# fpga.net
KiCad netlist of a schematic drawn in Altium Designer
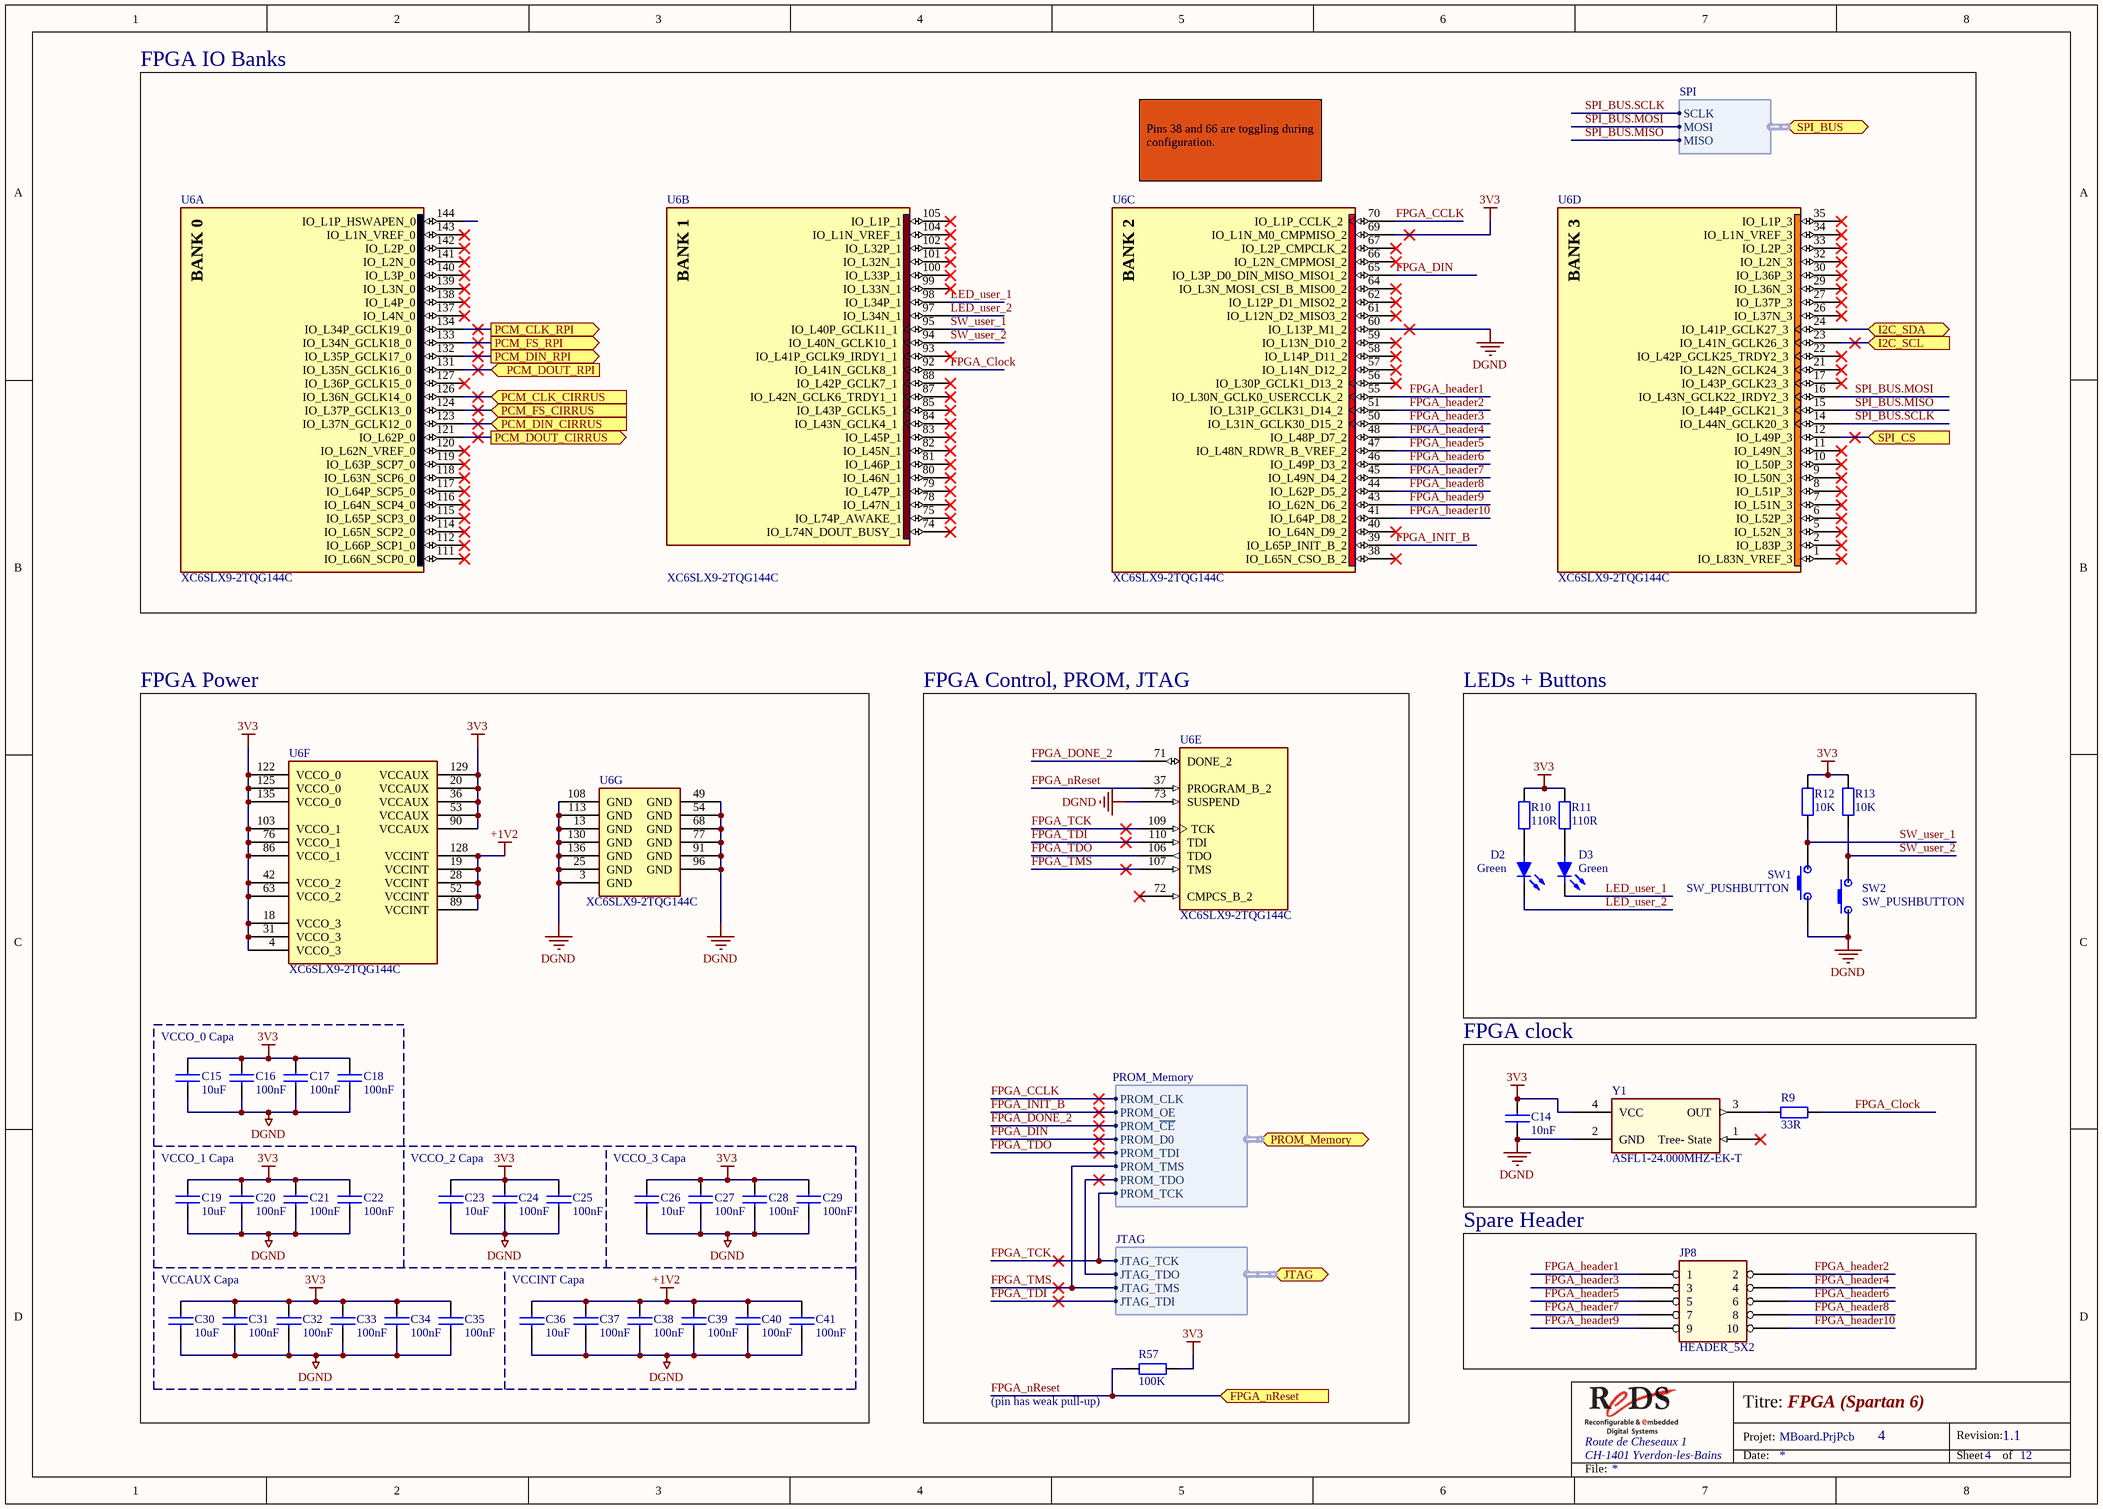
[diagram p0: fpga.SchDoc]

(export (version "E")
  (design (tool "Eeschema 10.0.6"))
  (components
    (comp (ref "C14")
      (value "10nF")
      (footprint "SM/C_0603")
      (description "Capacitor, ceramic")
      (fields (field (name "MANUFACTURER") "Kemet ") (field (name "VOLTAGE") "50V"))
      (libsource (lib "Database_heig-vd") (part "Cap"))
    )
    (comp (ref "C15")
      (value "10uF")
      (footprint "SM/C_1206")
      (description "Chip Monolithic Ceramic Capacitor")
      (fields (field (name "MANUFACTURER") "muRata") (field (name "VOLTAGE") "35V"))
      (libsource (lib "Database_heig-vd") (part "Cap"))
    )
    (comp (ref "C16")
      (value "100nF")
      (footprint "SM/C_0603")
      (description "Ceramic multi-layer")
      (fields (field (name "MANUFACTURER") "AVX") (field (name "VOLTAGE") "16V"))
      (libsource (lib "Database_heig-vd") (part "Cap"))
    )
    (comp (ref "C17")
      (value "100nF")
      (footprint "SM/C_0603")
      (description "Ceramic multi-layer")
      (fields (field (name "MANUFACTURER") "AVX") (field (name "VOLTAGE") "16V"))
      (libsource (lib "Database_heig-vd") (part "Cap"))
    )
    (comp (ref "C18")
      (value "100nF")
      (footprint "SM/C_0603")
      (description "Ceramic multi-layer")
      (fields (field (name "MANUFACTURER") "AVX") (field (name "VOLTAGE") "16V"))
      (libsource (lib "Database_heig-vd") (part "Cap"))
    )
    (comp (ref "C19")
      (value "10uF")
      (footprint "SM/C_1206")
      (description "Chip Monolithic Ceramic Capacitor")
      (fields (field (name "MANUFACTURER") "muRata") (field (name "VOLTAGE") "35V"))
      (libsource (lib "Database_heig-vd") (part "Cap"))
    )
    (comp (ref "C20")
      (value "100nF")
      (footprint "SM/C_0603")
      (description "Ceramic multi-layer")
      (fields (field (name "MANUFACTURER") "AVX") (field (name "VOLTAGE") "16V"))
      (libsource (lib "Database_heig-vd") (part "Cap"))
    )
    (comp (ref "C21")
      (value "100nF")
      (footprint "SM/C_0603")
      (description "Ceramic multi-layer")
      (fields (field (name "MANUFACTURER") "AVX") (field (name "VOLTAGE") "16V"))
      (libsource (lib "Database_heig-vd") (part "Cap"))
    )
    (comp (ref "C22")
      (value "100nF")
      (footprint "SM/C_0603")
      (description "Ceramic multi-layer")
      (fields (field (name "MANUFACTURER") "AVX") (field (name "VOLTAGE") "16V"))
      (libsource (lib "Database_heig-vd") (part "Cap"))
    )
    (comp (ref "C23")
      (value "10uF")
      (footprint "SM/C_1206")
      (description "Chip Monolithic Ceramic Capacitor")
      (fields (field (name "MANUFACTURER") "muRata") (field (name "VOLTAGE") "35V"))
      (libsource (lib "Database_heig-vd") (part "Cap"))
    )
    (comp (ref "C24")
      (value "100nF")
      (footprint "SM/C_0603")
      (description "Ceramic multi-layer")
      (fields (field (name "MANUFACTURER") "AVX") (field (name "VOLTAGE") "16V"))
      (libsource (lib "Database_heig-vd") (part "Cap"))
    )
    (comp (ref "C25")
      (value "100nF")
      (footprint "SM/C_0603")
      (description "Ceramic multi-layer")
      (fields (field (name "MANUFACTURER") "AVX") (field (name "VOLTAGE") "16V"))
      (libsource (lib "Database_heig-vd") (part "Cap"))
    )
    (comp (ref "C26")
      (value "10uF")
      (footprint "SM/C_1206")
      (description "Chip Monolithic Ceramic Capacitor")
      (fields (field (name "MANUFACTURER") "muRata") (field (name "VOLTAGE") "35V"))
      (libsource (lib "Database_heig-vd") (part "Cap"))
    )
    (comp (ref "C27")
      (value "100nF")
      (footprint "SM/C_0603")
      (description "Ceramic multi-layer")
      (fields (field (name "MANUFACTURER") "AVX") (field (name "VOLTAGE") "16V"))
      (libsource (lib "Database_heig-vd") (part "Cap"))
    )
    (comp (ref "C28")
      (value "100nF")
      (footprint "SM/C_0603")
      (description "Ceramic multi-layer")
      (fields (field (name "MANUFACTURER") "AVX") (field (name "VOLTAGE") "16V"))
      (libsource (lib "Database_heig-vd") (part "Cap"))
    )
    (comp (ref "C29")
      (value "100nF")
      (footprint "SM/C_0603")
      (description "Ceramic multi-layer")
      (fields (field (name "MANUFACTURER") "AVX") (field (name "VOLTAGE") "16V"))
      (libsource (lib "Database_heig-vd") (part "Cap"))
    )
    (comp (ref "C30")
      (value "10uF")
      (footprint "SM/C_1206")
      (description "Chip Monolithic Ceramic Capacitor")
      (fields (field (name "MANUFACTURER") "muRata") (field (name "VOLTAGE") "35V"))
      (libsource (lib "Database_heig-vd") (part "Cap"))
    )
    (comp (ref "C31")
      (value "100nF")
      (footprint "SM/C_0603")
      (description "Ceramic multi-layer")
      (fields (field (name "MANUFACTURER") "AVX") (field (name "VOLTAGE") "16V"))
      (libsource (lib "Database_heig-vd") (part "Cap"))
    )
    (comp (ref "C32")
      (value "100nF")
      (footprint "SM/C_0603")
      (description "Ceramic multi-layer")
      (fields (field (name "MANUFACTURER") "AVX") (field (name "VOLTAGE") "16V"))
      (libsource (lib "Database_heig-vd") (part "Cap"))
    )
    (comp (ref "C33")
      (value "100nF")
      (footprint "SM/C_0603")
      (description "Ceramic multi-layer")
      (fields (field (name "MANUFACTURER") "AVX") (field (name "VOLTAGE") "16V"))
      (libsource (lib "Database_heig-vd") (part "Cap"))
    )
    (comp (ref "C34")
      (value "100nF")
      (footprint "SM/C_0603")
      (description "Ceramic multi-layer")
      (fields (field (name "MANUFACTURER") "AVX") (field (name "VOLTAGE") "16V"))
      (libsource (lib "Database_heig-vd") (part "Cap"))
    )
    (comp (ref "C35")
      (value "100nF")
      (footprint "SM/C_0603")
      (description "Ceramic multi-layer")
      (fields (field (name "MANUFACTURER") "AVX") (field (name "VOLTAGE") "16V"))
      (libsource (lib "Database_heig-vd") (part "Cap"))
    )
    (comp (ref "C36")
      (value "10uF")
      (footprint "SM/C_1206")
      (description "Chip Monolithic Ceramic Capacitor")
      (fields (field (name "MANUFACTURER") "muRata") (field (name "VOLTAGE") "35V"))
      (libsource (lib "Database_heig-vd") (part "Cap"))
    )
    (comp (ref "C37")
      (value "100nF")
      (footprint "SM/C_0603")
      (description "Ceramic multi-layer")
      (fields (field (name "MANUFACTURER") "AVX") (field (name "VOLTAGE") "16V"))
      (libsource (lib "Database_heig-vd") (part "Cap"))
    )
    (comp (ref "C38")
      (value "100nF")
      (footprint "SM/C_0603")
      (description "Ceramic multi-layer")
      (fields (field (name "MANUFACTURER") "AVX") (field (name "VOLTAGE") "16V"))
      (libsource (lib "Database_heig-vd") (part "Cap"))
    )
    (comp (ref "C39")
      (value "100nF")
      (footprint "SM/C_0603")
      (description "Ceramic multi-layer")
      (fields (field (name "MANUFACTURER") "AVX") (field (name "VOLTAGE") "16V"))
      (libsource (lib "Database_heig-vd") (part "Cap"))
    )
    (comp (ref "C40")
      (value "100nF")
      (footprint "SM/C_0603")
      (description "Ceramic multi-layer")
      (fields (field (name "MANUFACTURER") "AVX") (field (name "VOLTAGE") "16V"))
      (libsource (lib "Database_heig-vd") (part "Cap"))
    )
    (comp (ref "C41")
      (value "100nF")
      (footprint "SM/C_0603")
      (description "Ceramic multi-layer")
      (fields (field (name "MANUFACTURER") "AVX") (field (name "VOLTAGE") "16V"))
      (libsource (lib "Database_heig-vd") (part "Cap"))
    )
    (comp (ref "D2")
      (value "Green")
      (footprint "PLCC_2")
      (description "SMT LED Green, Single Color PLCC-2 Type")
      (fields (field (name "MANUFACTURER") "Broadcom/Avago") (field (name "VOLTAGE") "2,2V"))
      (libsource (lib "Database_heig-vd") (part "Led"))
    )
    (comp (ref "D3")
      (value "Green")
      (footprint "PLCC_2")
      (description "SMT LED Green, Single Color PLCC-2 Type")
      (fields (field (name "MANUFACTURER") "Broadcom/Avago") (field (name "VOLTAGE") "2,2V"))
      (libsource (lib "Database_heig-vd") (part "Led"))
    )
    (comp (ref "JP8")
      (value "HEADER_5X2")
      (footprint "BLKCON.100/VH/TM2OE/W.200/10")
      (description "Barrette double 2x5 poles 2.54mm")
      (fields (field (name "MANUFACTURER") "TE Connectivity"))
      (libsource (lib "Database_heig-vd") (part "HEADER_5X2"))
    )
    (comp (ref "R9")
      (value "33R")
      (footprint "SM/R_0603")
      (description "Résistance 0603 63mW 1% 33R")
      (fields (field (name "MANUFACTURER") "Multicomp") (field (name "POWER") "63mW"))
      (libsource (lib "Database_heig-vd") (part "Res"))
    )
    (comp (ref "R10")
      (value "110R")
      (footprint "SM/R_0603")
      (description "Résistance 0603 63mW 1% 110R")
      (fields (field (name "MANUFACTURER") "Multicomp") (field (name "POWER") "63mW"))
      (libsource (lib "Database_heig-vd") (part "Res"))
    )
    (comp (ref "R11")
      (value "110R")
      (footprint "SM/R_0603")
      (description "Résistance 0603 63mW 1% 110R")
      (fields (field (name "MANUFACTURER") "Multicomp") (field (name "POWER") "63mW"))
      (libsource (lib "Database_heig-vd") (part "Res"))
    )
    (comp (ref "R12")
      (value "10K")
      (footprint "SM/R_0603")
      (description "Résistance 0603 63mW 1% 10K")
      (fields (field (name "MANUFACTURER") "Multicomp") (field (name "POWER") "63mW"))
      (libsource (lib "Database_heig-vd") (part "Res"))
    )
    (comp (ref "R13")
      (value "10K")
      (footprint "SM/R_0603")
      (description "Résistance 0603 63mW 1% 10K")
      (fields (field (name "MANUFACTURER") "Multicomp") (field (name "POWER") "63mW"))
      (libsource (lib "Database_heig-vd") (part "Res"))
    )
    (comp (ref "R57")
      (value "100K")
      (footprint "SM/R_0603")
      (description "Résistance 0603 63mW 1% 100K")
      (fields (field (name "MANUFACTURER") "Multicomp") (field (name "POWER") "63mW"))
      (libsource (lib "Database_heig-vd") (part "Res"))
    )
    (comp (ref "SW1")
      (value "SW_PUSHBUTTON")
      (footprint "TE Connectivity_SWITCH_SERIES-FSMSM")
      (description "SWITCH TACTILE SPST-NO 0.05A 12V")
      (fields (field (name "MANUFACTURER") "TE Connectivity") (field (name "VOLTAGE") "12V"))
      (libsource (lib "Database_heig-vd") (part "SW_PUSHBUTTON"))
    )
    (comp (ref "SW2")
      (value "SW_PUSHBUTTON")
      (footprint "TE Connectivity_SWITCH_SERIES-FSMSM")
      (description "SWITCH TACTILE SPST-NO 0.05A 12V")
      (fields (field (name "MANUFACTURER") "TE Connectivity") (field (name "VOLTAGE") "12V"))
      (libsource (lib "Database_heig-vd") (part "SW_PUSHBUTTON"))
    )
    (comp (ref "U6")
      (value "XC6SLX9-2TQG144C")
      (footprint "TQFP-144")
      (fields (field (name "MANUFACTURER") "Xilinx"))
      (libsource (lib "Database_heig-vd") (part "XC6SLX9-2TQG144C"))
    )
    (comp (ref "Y1")
      (value "OSCILLATOR_2")
      (footprint "ABRACON_OSCILLATOR_ASFL1 SERIES")
      (description "Oscillateur SMD 5mmx3.2mmx0.85mm")
      (fields
        (field (name "MANUFACTURER") "ABRACON Corporation")
        (field (name "MANUFACTURER P/N") "ASFL1-24.000MHZ-EK-T")
        (field (name "VOLTAGE") "3.3V")
      )
      (libsource (lib "Database_heig-vd") (part "OSCILLATOR_2"))
    )
  )
  (nets
    (net (code "4") (name "+1V2") (class "Default")
      (node (ref "C36") (pin "1") (pinfunction "1_1") (pintype "passive"))
      (node (ref "C37") (pin "1") (pinfunction "1_1") (pintype "passive"))
      (node (ref "C38") (pin "1") (pinfunction "1_1") (pintype "passive"))
      (node (ref "C39") (pin "1") (pinfunction "1_1") (pintype "passive"))
      (node (ref "C40") (pin "1") (pinfunction "1_1") (pintype "passive"))
      (node (ref "C41") (pin "1") (pinfunction "1_1") (pintype "passive"))
      (node (ref "U6") (pin "128") (pinfunction "VCCINT_128") (pintype "power_in"))
      (node (ref "U6") (pin "19") (pinfunction "VCCINT_19") (pintype "power_in"))
      (node (ref "U6") (pin "28") (pinfunction "VCCINT_28") (pintype "power_in"))
      (node (ref "U6") (pin "52") (pinfunction "VCCINT_52") (pintype "power_in"))
      (node (ref "U6") (pin "89") (pinfunction "VCCINT_89") (pintype "power_in"))
    )
    (net (code "5") (name "/FPGA_CCLK") (class "Default")
      (node (ref "U6") (pin "70") (pinfunction "IO_L1P_CCLK_2_70") (pintype "bidirectional"))
    )
    (net (code "6") (name "/FPGA_Clock") (class "Default")
      (node (ref "R9") (pin "2") (pinfunction "2_2") (pintype "passive"))
      (node (ref "U6") (pin "92") (pinfunction "IO_L41N_GCLK8_1_92") (pintype "bidirectional"))
    )
    (net (code "7") (name "/FPGA_DIN") (class "Default")
      (node (ref "U6") (pin "65") (pinfunction "IO_L3P_D0_DIN_MISO_MISO1_2_65") (pintype "bidirectional"))
    )
    (net (code "8") (name "/FPGA_DONE_2") (class "Default")
      (node (ref "U6") (pin "71") (pinfunction "DONE_2_71") (pintype "bidirectional"))
    )
    (net (code "9") (name "/FPGA_INIT_B") (class "Default")
      (node (ref "U6") (pin "39") (pinfunction "IO_L65P_INIT_B_2_39") (pintype "bidirectional"))
    )
    (net (code "10") (name "/FPGA_TCK") (class "Default")
      (node (ref "U6") (pin "109") (pinfunction "TCK_109") (pintype "input"))
    )
    (net (code "11") (name "/FPGA_TDI") (class "Default")
      (node (ref "U6") (pin "110") (pinfunction "TDI_110") (pintype "input"))
    )
    (net (code "12") (name "/FPGA_TDO") (class "Default")
      (node (ref "U6") (pin "106") (pinfunction "TDO_106") (pintype "output"))
    )
    (net (code "13") (name "/FPGA_TMS") (class "Default")
      (node (ref "U6") (pin "107") (pinfunction "TMS_107") (pintype "input"))
    )
    (net (code "14") (name "/FPGA_header1") (class "Default")
      (node (ref "JP8") (pin "1") (pinfunction "1_1") (pintype "passive"))
      (node (ref "U6") (pin "55") (pinfunction "IO_L30N_GCLK0_USERCCLK_2_55") (pintype "bidirectional"))
    )
    (net (code "15") (name "/FPGA_header2") (class "Default")
      (node (ref "JP8") (pin "2") (pinfunction "2_2") (pintype "passive"))
      (node (ref "U6") (pin "51") (pinfunction "IO_L31P_GCLK31_D14_2_51") (pintype "bidirectional"))
    )
    (net (code "16") (name "/FPGA_header3") (class "Default")
      (node (ref "JP8") (pin "3") (pinfunction "3_3") (pintype "passive"))
      (node (ref "U6") (pin "50") (pinfunction "IO_L31N_GCLK30_D15_2_50") (pintype "bidirectional"))
    )
    (net (code "17") (name "/FPGA_header4") (class "Default")
      (node (ref "JP8") (pin "4") (pinfunction "4_4") (pintype "passive"))
      (node (ref "U6") (pin "48") (pinfunction "IO_L48P_D7_2_48") (pintype "bidirectional"))
    )
    (net (code "18") (name "/FPGA_header5") (class "Default")
      (node (ref "JP8") (pin "5") (pinfunction "5_5") (pintype "passive"))
      (node (ref "U6") (pin "47") (pinfunction "IO_L48N_RDWR_B_VREF_2_47") (pintype "bidirectional"))
    )
    (net (code "19") (name "/FPGA_header6") (class "Default")
      (node (ref "JP8") (pin "6") (pinfunction "6_6") (pintype "passive"))
      (node (ref "U6") (pin "46") (pinfunction "IO_L49P_D3_2_46") (pintype "bidirectional"))
    )
    (net (code "20") (name "/FPGA_header7") (class "Default")
      (node (ref "JP8") (pin "7") (pinfunction "7_7") (pintype "passive"))
      (node (ref "U6") (pin "45") (pinfunction "IO_L49N_D4_2_45") (pintype "bidirectional"))
    )
    (net (code "21") (name "/FPGA_header8") (class "Default")
      (node (ref "JP8") (pin "8") (pinfunction "8_8") (pintype "passive"))
      (node (ref "U6") (pin "44") (pinfunction "IO_L62P_D5_2_44") (pintype "bidirectional"))
    )
    (net (code "22") (name "/FPGA_header9") (class "Default")
      (node (ref "JP8") (pin "9") (pinfunction "9_9") (pintype "passive"))
      (node (ref "U6") (pin "43") (pinfunction "IO_L62N_D6_2_43") (pintype "bidirectional"))
    )
    (net (code "23") (name "/FPGA_header10") (class "Default")
      (node (ref "JP8") (pin "10") (pinfunction "10_10") (pintype "passive"))
      (node (ref "U6") (pin "41") (pinfunction "IO_L64P_D8_2_41") (pintype "bidirectional"))
    )
    (net (code "24") (name "/FPGA_nReset") (class "Default")
      (node (ref "R57") (pin "1") (pinfunction "1_1") (pintype "passive"))
      (node (ref "U6") (pin "37") (pinfunction "PROGRAM_B_2_37") (pintype "input"))
    )
    (net (code "25") (name "/I2C_SCL") (class "Default")
      (node (ref "U6") (pin "23") (pinfunction "IO_L41N_GCLK26_3_23") (pintype "bidirectional"))
    )
    (net (code "26") (name "/I2C_SDA") (class "Default")
      (node (ref "U6") (pin "24") (pinfunction "IO_L41P_GCLK27_3_24") (pintype "bidirectional"))
    )
    (net (code "27") (name "/LED_user_1") (class "Default")
      (node (ref "D3") (pin "2") (pinfunction "C_2") (pintype "passive"))
      (node (ref "U6") (pin "98") (pinfunction "IO_L34P_1_98") (pintype "bidirectional"))
    )
    (net (code "28") (name "/LED_user_2") (class "Default")
      (node (ref "D2") (pin "2") (pinfunction "C_2") (pintype "passive"))
      (node (ref "U6") (pin "97") (pinfunction "IO_L34N_1_97") (pintype "bidirectional"))
    )
    (net (code "29") (name "/PCM_CLK_CIRRUS") (class "Default")
      (node (ref "U6") (pin "126") (pinfunction "IO_L36N_GCLK14_0_126") (pintype "bidirectional"))
    )
    (net (code "30") (name "/PCM_CLK_RPI") (class "Default")
      (node (ref "U6") (pin "134") (pinfunction "IO_L34P_GCLK19_0_134") (pintype "bidirectional"))
    )
    (net (code "31") (name "/PCM_DIN_CIRRUS") (class "Default")
      (node (ref "U6") (pin "123") (pinfunction "IO_L37N_GCLK12_0_123") (pintype "bidirectional"))
    )
    (net (code "32") (name "/PCM_DIN_RPI") (class "Default")
      (node (ref "U6") (pin "132") (pinfunction "IO_L35P_GCLK17_0_132") (pintype "bidirectional"))
    )
    (net (code "33") (name "/PCM_DOUT_CIRRUS") (class "Default")
      (node (ref "U6") (pin "121") (pinfunction "IO_L62P_0_121") (pintype "bidirectional"))
    )
    (net (code "34") (name "/PCM_DOUT_RPI") (class "Default")
      (node (ref "U6") (pin "131") (pinfunction "IO_L35N_GCLK16_0_131") (pintype "bidirectional"))
    )
    (net (code "35") (name "/PCM_FS_CIRRUS") (class "Default")
      (node (ref "U6") (pin "124") (pinfunction "IO_L37P_GCLK13_0_124") (pintype "bidirectional"))
    )
    (net (code "36") (name "/PCM_FS_RPI") (class "Default")
      (node (ref "U6") (pin "133") (pinfunction "IO_L34N_GCLK18_0_133") (pintype "bidirectional"))
    )
    (net (code "37") (name "/SPI_BUS.MISO") (class "Default")
      (node (ref "U6") (pin "15") (pinfunction "IO_L44P_GCLK21_3_15") (pintype "bidirectional"))
    )
    (net (code "38") (name "/SPI_BUS.MOSI") (class "Default")
      (node (ref "U6") (pin "16") (pinfunction "IO_L43N_GCLK22_IRDY2_3_16") (pintype "bidirectional"))
    )
    (net (code "39") (name "/SPI_BUS.SCLK") (class "Default")
      (node (ref "U6") (pin "14") (pinfunction "IO_L44N_GCLK20_3_14") (pintype "bidirectional"))
    )
    (net (code "40") (name "/SPI_CS") (class "Default")
      (node (ref "U6") (pin "12") (pinfunction "IO_L49P_3_12") (pintype "bidirectional"))
    )
    (net (code "41") (name "/SW_user_1") (class "Default")
      (node (ref "R12") (pin "2") (pinfunction "2_2") (pintype "passive"))
      (node (ref "SW1") (pin "2") (pinfunction "2_2") (pintype "passive"))
      (node (ref "U6") (pin "95") (pinfunction "IO_L40P_GCLK11_1_95") (pintype "bidirectional"))
    )
    (net (code "42") (name "/SW_user_2") (class "Default")
      (node (ref "R13") (pin "2") (pinfunction "2_2") (pintype "passive"))
      (node (ref "SW2") (pin "2") (pinfunction "2_2") (pintype "passive"))
      (node (ref "U6") (pin "94") (pinfunction "IO_L40N_GCLK10_1_94") (pintype "bidirectional"))
    )
    (net (code "46") (name "3V3") (class "Default")
      (node (ref "C14") (pin "1") (pinfunction "1_1") (pintype "passive"))
      (node (ref "C15") (pin "1") (pinfunction "1_1") (pintype "passive"))
      (node (ref "C16") (pin "1") (pinfunction "1_1") (pintype "passive"))
      (node (ref "C17") (pin "1") (pinfunction "1_1") (pintype "passive"))
      (node (ref "C18") (pin "1") (pinfunction "1_1") (pintype "passive"))
      (node (ref "C19") (pin "1") (pinfunction "1_1") (pintype "passive"))
      (node (ref "C20") (pin "1") (pinfunction "1_1") (pintype "passive"))
      (node (ref "C21") (pin "1") (pinfunction "1_1") (pintype "passive"))
      (node (ref "C22") (pin "1") (pinfunction "1_1") (pintype "passive"))
      (node (ref "C23") (pin "1") (pinfunction "1_1") (pintype "passive"))
      (node (ref "C24") (pin "1") (pinfunction "1_1") (pintype "passive"))
      (node (ref "C25") (pin "1") (pinfunction "1_1") (pintype "passive"))
      (node (ref "C26") (pin "1") (pinfunction "1_1") (pintype "passive"))
      (node (ref "C27") (pin "1") (pinfunction "1_1") (pintype "passive"))
      (node (ref "C28") (pin "1") (pinfunction "1_1") (pintype "passive"))
      (node (ref "C29") (pin "1") (pinfunction "1_1") (pintype "passive"))
      (node (ref "C30") (pin "1") (pinfunction "1_1") (pintype "passive"))
      (node (ref "C31") (pin "1") (pinfunction "1_1") (pintype "passive"))
      (node (ref "C32") (pin "1") (pinfunction "1_1") (pintype "passive"))
      (node (ref "C33") (pin "1") (pinfunction "1_1") (pintype "passive"))
      (node (ref "C34") (pin "1") (pinfunction "1_1") (pintype "passive"))
      (node (ref "C35") (pin "1") (pinfunction "1_1") (pintype "passive"))
      (node (ref "R10") (pin "1") (pinfunction "1_1") (pintype "passive"))
      (node (ref "R11") (pin "1") (pinfunction "1_1") (pintype "passive"))
      (node (ref "R12") (pin "1") (pinfunction "1_1") (pintype "passive"))
      (node (ref "R13") (pin "1") (pinfunction "1_1") (pintype "passive"))
      (node (ref "R57") (pin "2") (pinfunction "2_2") (pintype "passive"))
      (node (ref "U6") (pin "103") (pinfunction "VCCO_1_103") (pintype "power_in"))
      (node (ref "U6") (pin "122") (pinfunction "VCCO_0_122") (pintype "power_in"))
      (node (ref "U6") (pin "125") (pinfunction "VCCO_0_125") (pintype "power_in"))
      (node (ref "U6") (pin "129") (pinfunction "VCCAUX_129") (pintype "power_in"))
      (node (ref "U6") (pin "135") (pinfunction "VCCO_0_135") (pintype "power_in"))
      (node (ref "U6") (pin "18") (pinfunction "VCCO_3_18") (pintype "power_in"))
      (node (ref "U6") (pin "20") (pinfunction "VCCAUX_20") (pintype "power_in"))
      (node (ref "U6") (pin "31") (pinfunction "VCCO_3_31") (pintype "power_in"))
      (node (ref "U6") (pin "36") (pinfunction "VCCAUX_36") (pintype "power_in"))
      (node (ref "U6") (pin "4") (pinfunction "VCCO_3_4") (pintype "power_in"))
      (node (ref "U6") (pin "42") (pinfunction "VCCO_2_42") (pintype "power_in"))
      (node (ref "U6") (pin "53") (pinfunction "VCCAUX_53") (pintype "power_in"))
      (node (ref "U6") (pin "63") (pinfunction "VCCO_2_63") (pintype "power_in"))
      (node (ref "U6") (pin "69") (pinfunction "IO_L1N_M0_CMPMISO_2_69") (pintype "bidirectional"))
      (node (ref "U6") (pin "76") (pinfunction "VCCO_1_76") (pintype "power_in"))
      (node (ref "U6") (pin "86") (pinfunction "VCCO_1_86") (pintype "power_in"))
      (node (ref "U6") (pin "90") (pinfunction "VCCAUX_90") (pintype "power_in"))
      (node (ref "Y1") (pin "4") (pinfunction "VCC_4") (pintype "power_in"))
    )
    (net (code "47") (name "DGND") (class "Default")
      (node (ref "C14") (pin "2") (pinfunction "2_2") (pintype "passive"))
      (node (ref "C15") (pin "2") (pinfunction "2_2") (pintype "passive"))
      (node (ref "C16") (pin "2") (pinfunction "2_2") (pintype "passive"))
      (node (ref "C17") (pin "2") (pinfunction "2_2") (pintype "passive"))
      (node (ref "C18") (pin "2") (pinfunction "2_2") (pintype "passive"))
      (node (ref "C19") (pin "2") (pinfunction "2_2") (pintype "passive"))
      (node (ref "C20") (pin "2") (pinfunction "2_2") (pintype "passive"))
      (node (ref "C21") (pin "2") (pinfunction "2_2") (pintype "passive"))
      (node (ref "C22") (pin "2") (pinfunction "2_2") (pintype "passive"))
      (node (ref "C23") (pin "2") (pinfunction "2_2") (pintype "passive"))
      (node (ref "C24") (pin "2") (pinfunction "2_2") (pintype "passive"))
      (node (ref "C25") (pin "2") (pinfunction "2_2") (pintype "passive"))
      (node (ref "C26") (pin "2") (pinfunction "2_2") (pintype "passive"))
      (node (ref "C27") (pin "2") (pinfunction "2_2") (pintype "passive"))
      (node (ref "C28") (pin "2") (pinfunction "2_2") (pintype "passive"))
      (node (ref "C29") (pin "2") (pinfunction "2_2") (pintype "passive"))
      (node (ref "C30") (pin "2") (pinfunction "2_2") (pintype "passive"))
      (node (ref "C31") (pin "2") (pinfunction "2_2") (pintype "passive"))
      (node (ref "C32") (pin "2") (pinfunction "2_2") (pintype "passive"))
      (node (ref "C33") (pin "2") (pinfunction "2_2") (pintype "passive"))
      (node (ref "C34") (pin "2") (pinfunction "2_2") (pintype "passive"))
      (node (ref "C35") (pin "2") (pinfunction "2_2") (pintype "passive"))
      (node (ref "C36") (pin "2") (pinfunction "2_2") (pintype "passive"))
      (node (ref "C37") (pin "2") (pinfunction "2_2") (pintype "passive"))
      (node (ref "C38") (pin "2") (pinfunction "2_2") (pintype "passive"))
      (node (ref "C39") (pin "2") (pinfunction "2_2") (pintype "passive"))
      (node (ref "C40") (pin "2") (pinfunction "2_2") (pintype "passive"))
      (node (ref "C41") (pin "2") (pinfunction "2_2") (pintype "passive"))
      (node (ref "SW1") (pin "1") (pinfunction "1_1") (pintype "passive"))
      (node (ref "SW2") (pin "1") (pinfunction "1_1") (pintype "passive"))
      (node (ref "U6") (pin "108") (pinfunction "GND_108") (pintype "power_in"))
      (node (ref "U6") (pin "113") (pinfunction "GND_113") (pintype "power_in"))
      (node (ref "U6") (pin "13") (pinfunction "GND_13") (pintype "power_in"))
      (node (ref "U6") (pin "130") (pinfunction "GND_130") (pintype "power_in"))
      (node (ref "U6") (pin "136") (pinfunction "GND_136") (pintype "power_in"))
      (node (ref "U6") (pin "25") (pinfunction "GND_25") (pintype "power_in"))
      (node (ref "U6") (pin "3") (pinfunction "GND_3") (pintype "power_in"))
      (node (ref "U6") (pin "49") (pinfunction "GND_49") (pintype "power_in"))
      (node (ref "U6") (pin "54") (pinfunction "GND_54") (pintype "power_in"))
      (node (ref "U6") (pin "60") (pinfunction "IO_L13P_M1_2_60") (pintype "bidirectional"))
      (node (ref "U6") (pin "68") (pinfunction "GND_68") (pintype "power_in"))
      (node (ref "U6") (pin "73") (pinfunction "SUSPEND_73") (pintype "input"))
      (node (ref "U6") (pin "77") (pinfunction "GND_77") (pintype "power_in"))
      (node (ref "U6") (pin "91") (pinfunction "GND_91") (pintype "power_in"))
      (node (ref "U6") (pin "96") (pinfunction "GND_96") (pintype "power_in"))
      (node (ref "Y1") (pin "2") (pinfunction "GND_2") (pintype "power_in"))
    )
    (net (code "48") (name "Net-(D2-A)") (class "Default")
      (node (ref "D2") (pin "1") (pinfunction "A_1") (pintype "passive"))
      (node (ref "R10") (pin "2") (pinfunction "2_2") (pintype "passive"))
    )
    (net (code "49") (name "Net-(D3-A)") (class "Default")
      (node (ref "D3") (pin "1") (pinfunction "A_1") (pintype "passive"))
      (node (ref "R11") (pin "2") (pinfunction "2_2") (pintype "passive"))
    )
    (net (code "50") (name "Net-(Y1-OUT)") (class "Default")
      (node (ref "R9") (pin "1") (pinfunction "1_1") (pintype "passive"))
      (node (ref "Y1") (pin "3") (pinfunction "OUT_3") (pintype "output"))
    )
    (net (code "51") (name "unconnected-(U6A-IO_L1N_VREF_0-Pad143)") (class "Default")
      (node (ref "U6") (pin "143") (pinfunction "IO_L1N_VREF_0_143") (pintype "bidirectional+no_connect"))
    )
    (net (code "52") (name "unconnected-(U6A-IO_L1P_HSWAPEN_0-Pad144)") (class "Default")
      (node (ref "U6") (pin "144") (pinfunction "IO_L1P_HSWAPEN_0_144") (pintype "bidirectional"))
    )
    (net (code "53") (name "unconnected-(U6A-IO_L2N_0-Pad141)") (class "Default")
      (node (ref "U6") (pin "141") (pinfunction "IO_L2N_0_141") (pintype "bidirectional+no_connect"))
    )
    (net (code "54") (name "unconnected-(U6A-IO_L2P_0-Pad142)") (class "Default")
      (node (ref "U6") (pin "142") (pinfunction "IO_L2P_0_142") (pintype "bidirectional+no_connect"))
    )
    (net (code "55") (name "unconnected-(U6A-IO_L3N_0-Pad139)") (class "Default")
      (node (ref "U6") (pin "139") (pinfunction "IO_L3N_0_139") (pintype "bidirectional+no_connect"))
    )
    (net (code "56") (name "unconnected-(U6A-IO_L3P_0-Pad140)") (class "Default")
      (node (ref "U6") (pin "140") (pinfunction "IO_L3P_0_140") (pintype "bidirectional+no_connect"))
    )
    (net (code "57") (name "unconnected-(U6A-IO_L4N_0-Pad137)") (class "Default")
      (node (ref "U6") (pin "137") (pinfunction "IO_L4N_0_137") (pintype "bidirectional+no_connect"))
    )
    (net (code "58") (name "unconnected-(U6A-IO_L4P_0-Pad138)") (class "Default")
      (node (ref "U6") (pin "138") (pinfunction "IO_L4P_0_138") (pintype "bidirectional+no_connect"))
    )
    (net (code "59") (name "unconnected-(U6A-IO_L36P_GCLK15_0-Pad127)") (class "Default")
      (node (ref "U6") (pin "127") (pinfunction "IO_L36P_GCLK15_0_127") (pintype "bidirectional+no_connect"))
    )
    (net (code "60") (name "unconnected-(U6A-IO_L62N_VREF_0-Pad120)") (class "Default")
      (node (ref "U6") (pin "120") (pinfunction "IO_L62N_VREF_0_120") (pintype "bidirectional+no_connect"))
    )
    (net (code "61") (name "unconnected-(U6A-IO_L63N_SCP6_0-Pad118)") (class "Default")
      (node (ref "U6") (pin "118") (pinfunction "IO_L63N_SCP6_0_118") (pintype "bidirectional+no_connect"))
    )
    (net (code "62") (name "unconnected-(U6A-IO_L63P_SCP7_0-Pad119)") (class "Default")
      (node (ref "U6") (pin "119") (pinfunction "IO_L63P_SCP7_0_119") (pintype "bidirectional+no_connect"))
    )
    (net (code "63") (name "unconnected-(U6A-IO_L64N_SCP4_0-Pad116)") (class "Default")
      (node (ref "U6") (pin "116") (pinfunction "IO_L64N_SCP4_0_116") (pintype "bidirectional+no_connect"))
    )
    (net (code "64") (name "unconnected-(U6A-IO_L64P_SCP5_0-Pad117)") (class "Default")
      (node (ref "U6") (pin "117") (pinfunction "IO_L64P_SCP5_0_117") (pintype "bidirectional+no_connect"))
    )
    (net (code "65") (name "unconnected-(U6A-IO_L65N_SCP2_0-Pad114)") (class "Default")
      (node (ref "U6") (pin "114") (pinfunction "IO_L65N_SCP2_0_114") (pintype "bidirectional+no_connect"))
    )
    (net (code "66") (name "unconnected-(U6A-IO_L65P_SCP3_0-Pad115)") (class "Default")
      (node (ref "U6") (pin "115") (pinfunction "IO_L65P_SCP3_0_115") (pintype "bidirectional+no_connect"))
    )
    (net (code "67") (name "unconnected-(U6A-IO_L66N_SCP0_0-Pad111)") (class "Default")
      (node (ref "U6") (pin "111") (pinfunction "IO_L66N_SCP0_0_111") (pintype "bidirectional+no_connect"))
    )
    (net (code "68") (name "unconnected-(U6A-IO_L66P_SCP1_0-Pad112)") (class "Default")
      (node (ref "U6") (pin "112") (pinfunction "IO_L66P_SCP1_0_112") (pintype "bidirectional+no_connect"))
    )
    (net (code "69") (name "unconnected-(U6B-IO_L1N_VREF_1-Pad104)") (class "Default")
      (node (ref "U6") (pin "104") (pinfunction "IO_L1N_VREF_1_104") (pintype "bidirectional+no_connect"))
    )
    (net (code "70") (name "unconnected-(U6B-IO_L1P_1-Pad105)") (class "Default")
      (node (ref "U6") (pin "105") (pinfunction "IO_L1P_1_105") (pintype "bidirectional+no_connect"))
    )
    (net (code "71") (name "unconnected-(U6B-IO_L32N_1-Pad101)") (class "Default")
      (node (ref "U6") (pin "101") (pinfunction "IO_L32N_1_101") (pintype "bidirectional+no_connect"))
    )
    (net (code "72") (name "unconnected-(U6B-IO_L32P_1-Pad102)") (class "Default")
      (node (ref "U6") (pin "102") (pinfunction "IO_L32P_1_102") (pintype "bidirectional+no_connect"))
    )
    (net (code "73") (name "unconnected-(U6B-IO_L33N_1-Pad99)") (class "Default")
      (node (ref "U6") (pin "99") (pinfunction "IO_L33N_1_99") (pintype "bidirectional+no_connect"))
    )
    (net (code "74") (name "unconnected-(U6B-IO_L33P_1-Pad100)") (class "Default")
      (node (ref "U6") (pin "100") (pinfunction "IO_L33P_1_100") (pintype "bidirectional+no_connect"))
    )
    (net (code "75") (name "unconnected-(U6B-IO_L41P_GCLK9_IRDY1_1-Pad93)") (class "Default")
      (node (ref "U6") (pin "93") (pinfunction "IO_L41P_GCLK9_IRDY1_1_93") (pintype "bidirectional+no_connect"))
    )
    (net (code "76") (name "unconnected-(U6B-IO_L42N_GCLK6_TRDY1_1-Pad87)") (class "Default")
      (node (ref "U6") (pin "87") (pinfunction "IO_L42N_GCLK6_TRDY1_1_87") (pintype "bidirectional+no_connect"))
    )
    (net (code "77") (name "unconnected-(U6B-IO_L42P_GCLK7_1-Pad88)") (class "Default")
      (node (ref "U6") (pin "88") (pinfunction "IO_L42P_GCLK7_1_88") (pintype "bidirectional+no_connect"))
    )
    (net (code "78") (name "unconnected-(U6B-IO_L43N_GCLK4_1-Pad84)") (class "Default")
      (node (ref "U6") (pin "84") (pinfunction "IO_L43N_GCLK4_1_84") (pintype "bidirectional+no_connect"))
    )
    (net (code "79") (name "unconnected-(U6B-IO_L43P_GCLK5_1-Pad85)") (class "Default")
      (node (ref "U6") (pin "85") (pinfunction "IO_L43P_GCLK5_1_85") (pintype "bidirectional+no_connect"))
    )
    (net (code "80") (name "unconnected-(U6B-IO_L45N_1-Pad82)") (class "Default")
      (node (ref "U6") (pin "82") (pinfunction "IO_L45N_1_82") (pintype "bidirectional+no_connect"))
    )
    (net (code "81") (name "unconnected-(U6B-IO_L45P_1-Pad83)") (class "Default")
      (node (ref "U6") (pin "83") (pinfunction "IO_L45P_1_83") (pintype "bidirectional+no_connect"))
    )
    (net (code "82") (name "unconnected-(U6B-IO_L46N_1-Pad80)") (class "Default")
      (node (ref "U6") (pin "80") (pinfunction "IO_L46N_1_80") (pintype "bidirectional+no_connect"))
    )
    (net (code "83") (name "unconnected-(U6B-IO_L46P_1-Pad81)") (class "Default")
      (node (ref "U6") (pin "81") (pinfunction "IO_L46P_1_81") (pintype "bidirectional+no_connect"))
    )
    (net (code "84") (name "unconnected-(U6B-IO_L47N_1-Pad78)") (class "Default")
      (node (ref "U6") (pin "78") (pinfunction "IO_L47N_1_78") (pintype "bidirectional+no_connect"))
    )
    (net (code "85") (name "unconnected-(U6B-IO_L47P_1-Pad79)") (class "Default")
      (node (ref "U6") (pin "79") (pinfunction "IO_L47P_1_79") (pintype "bidirectional+no_connect"))
    )
    (net (code "86") (name "unconnected-(U6B-IO_L74N_DOUT_BUSY_1-Pad74)") (class "Default")
      (node (ref "U6") (pin "74") (pinfunction "IO_L74N_DOUT_BUSY_1_74") (pintype "bidirectional+no_connect"))
    )
    (net (code "87") (name "unconnected-(U6B-IO_L74P_AWAKE_1-Pad75)") (class "Default")
      (node (ref "U6") (pin "75") (pinfunction "IO_L74P_AWAKE_1_75") (pintype "bidirectional+no_connect"))
    )
    (net (code "88") (name "unconnected-(U6C-IO_L2N_CMPMOSI_2-Pad66)") (class "Default")
      (node (ref "U6") (pin "66") (pinfunction "IO_L2N_CMPMOSI_2_66") (pintype "bidirectional+no_connect"))
    )
    (net (code "89") (name "unconnected-(U6C-IO_L2P_CMPCLK_2-Pad67)") (class "Default")
      (node (ref "U6") (pin "67") (pinfunction "IO_L2P_CMPCLK_2_67") (pintype "bidirectional+no_connect"))
    )
    (net (code "90") (name "unconnected-(U6C-IO_L3N_MOSI_CSI_B_MISO0_2-Pad64)") (class "Default")
      (node (ref "U6") (pin "64") (pinfunction "IO_L3N_MOSI_CSI_B_MISO0_2_64") (pintype "bidirectional+no_connect"))
    )
    (net (code "91") (name "unconnected-(U6C-IO_L12N_D2_MISO3_2-Pad61)") (class "Default")
      (node (ref "U6") (pin "61") (pinfunction "IO_L12N_D2_MISO3_2_61") (pintype "bidirectional+no_connect"))
    )
    (net (code "92") (name "unconnected-(U6C-IO_L12P_D1_MISO2_2-Pad62)") (class "Default")
      (node (ref "U6") (pin "62") (pinfunction "IO_L12P_D1_MISO2_2_62") (pintype "bidirectional+no_connect"))
    )
    (net (code "93") (name "unconnected-(U6C-IO_L13N_D10_2-Pad59)") (class "Default")
      (node (ref "U6") (pin "59") (pinfunction "IO_L13N_D10_2_59") (pintype "bidirectional+no_connect"))
    )
    (net (code "94") (name "unconnected-(U6C-IO_L14N_D12_2-Pad57)") (class "Default")
      (node (ref "U6") (pin "57") (pinfunction "IO_L14N_D12_2_57") (pintype "bidirectional+no_connect"))
    )
    (net (code "95") (name "unconnected-(U6C-IO_L14P_D11_2-Pad58)") (class "Default")
      (node (ref "U6") (pin "58") (pinfunction "IO_L14P_D11_2_58") (pintype "bidirectional+no_connect"))
    )
    (net (code "96") (name "unconnected-(U6C-IO_L30P_GCLK1_D13_2-Pad56)") (class "Default")
      (node (ref "U6") (pin "56") (pinfunction "IO_L30P_GCLK1_D13_2_56") (pintype "bidirectional+no_connect"))
    )
    (net (code "97") (name "unconnected-(U6C-IO_L64N_D9_2-Pad40)") (class "Default")
      (node (ref "U6") (pin "40") (pinfunction "IO_L64N_D9_2_40") (pintype "bidirectional+no_connect"))
    )
    (net (code "98") (name "unconnected-(U6C-IO_L65N_CSO_B_2-Pad38)") (class "Default")
      (node (ref "U6") (pin "38") (pinfunction "IO_L65N_CSO_B_2_38") (pintype "bidirectional+no_connect"))
    )
    (net (code "99") (name "unconnected-(U6D-IO_L1N_VREF_3-Pad34)") (class "Default")
      (node (ref "U6") (pin "34") (pinfunction "IO_L1N_VREF_3_34") (pintype "bidirectional+no_connect"))
    )
    (net (code "100") (name "unconnected-(U6D-IO_L1P_3-Pad35)") (class "Default")
      (node (ref "U6") (pin "35") (pinfunction "IO_L1P_3_35") (pintype "bidirectional+no_connect"))
    )
    (net (code "101") (name "unconnected-(U6D-IO_L2N_3-Pad32)") (class "Default")
      (node (ref "U6") (pin "32") (pinfunction "IO_L2N_3_32") (pintype "bidirectional+no_connect"))
    )
    (net (code "102") (name "unconnected-(U6D-IO_L2P_3-Pad33)") (class "Default")
      (node (ref "U6") (pin "33") (pinfunction "IO_L2P_3_33") (pintype "bidirectional+no_connect"))
    )
    (net (code "103") (name "unconnected-(U6D-IO_L36N_3-Pad29)") (class "Default")
      (node (ref "U6") (pin "29") (pinfunction "IO_L36N_3_29") (pintype "bidirectional+no_connect"))
    )
    (net (code "104") (name "unconnected-(U6D-IO_L36P_3-Pad30)") (class "Default")
      (node (ref "U6") (pin "30") (pinfunction "IO_L36P_3_30") (pintype "bidirectional+no_connect"))
    )
    (net (code "105") (name "unconnected-(U6D-IO_L37N_3-Pad26)") (class "Default")
      (node (ref "U6") (pin "26") (pinfunction "IO_L37N_3_26") (pintype "bidirectional+no_connect"))
    )
    (net (code "106") (name "unconnected-(U6D-IO_L37P_3-Pad27)") (class "Default")
      (node (ref "U6") (pin "27") (pinfunction "IO_L37P_3_27") (pintype "bidirectional+no_connect"))
    )
    (net (code "107") (name "unconnected-(U6D-IO_L42N_GCLK24_3-Pad21)") (class "Default")
      (node (ref "U6") (pin "21") (pinfunction "IO_L42N_GCLK24_3_21") (pintype "bidirectional+no_connect"))
    )
    (net (code "108") (name "unconnected-(U6D-IO_L42P_GCLK25_TRDY2_3-Pad22)") (class "Default")
      (node (ref "U6") (pin "22") (pinfunction "IO_L42P_GCLK25_TRDY2_3_22") (pintype "bidirectional+no_connect"))
    )
    (net (code "109") (name "unconnected-(U6D-IO_L43P_GCLK23_3-Pad17)") (class "Default")
      (node (ref "U6") (pin "17") (pinfunction "IO_L43P_GCLK23_3_17") (pintype "bidirectional+no_connect"))
    )
    (net (code "110") (name "unconnected-(U6D-IO_L49N_3-Pad11)") (class "Default")
      (node (ref "U6") (pin "11") (pinfunction "IO_L49N_3_11") (pintype "bidirectional+no_connect"))
    )
    (net (code "111") (name "unconnected-(U6D-IO_L50N_3-Pad9)") (class "Default")
      (node (ref "U6") (pin "9") (pinfunction "IO_L50N_3_9") (pintype "bidirectional+no_connect"))
    )
    (net (code "112") (name "unconnected-(U6D-IO_L50P_3-Pad10)") (class "Default")
      (node (ref "U6") (pin "10") (pinfunction "IO_L50P_3_10") (pintype "bidirectional+no_connect"))
    )
    (net (code "113") (name "unconnected-(U6D-IO_L51N_3-Pad7)") (class "Default")
      (node (ref "U6") (pin "7") (pinfunction "IO_L51N_3_7") (pintype "bidirectional+no_connect"))
    )
    (net (code "114") (name "unconnected-(U6D-IO_L51P_3-Pad8)") (class "Default")
      (node (ref "U6") (pin "8") (pinfunction "IO_L51P_3_8") (pintype "bidirectional+no_connect"))
    )
    (net (code "115") (name "unconnected-(U6D-IO_L52N_3-Pad5)") (class "Default")
      (node (ref "U6") (pin "5") (pinfunction "IO_L52N_3_5") (pintype "bidirectional+no_connect"))
    )
    (net (code "116") (name "unconnected-(U6D-IO_L52P_3-Pad6)") (class "Default")
      (node (ref "U6") (pin "6") (pinfunction "IO_L52P_3_6") (pintype "bidirectional+no_connect"))
    )
    (net (code "117") (name "unconnected-(U6D-IO_L83N_VREF_3-Pad1)") (class "Default")
      (node (ref "U6") (pin "1") (pinfunction "IO_L83N_VREF_3_1") (pintype "bidirectional+no_connect"))
    )
    (net (code "118") (name "unconnected-(U6D-IO_L83P_3-Pad2)") (class "Default")
      (node (ref "U6") (pin "2") (pinfunction "IO_L83P_3_2") (pintype "bidirectional+no_connect"))
    )
    (net (code "119") (name "unconnected-(U6E-CMPCS_B_2-Pad72)") (class "Default")
      (node (ref "U6") (pin "72") (pinfunction "CMPCS_B_2_72") (pintype "input+no_connect"))
    )
    (net (code "120") (name "unconnected-(Y1-Tree-_State-Pad1)") (class "Default")
      (node (ref "Y1") (pin "1") (pinfunction "Tree-_State_1") (pintype "input+no_connect"))
    )
  )
)
